# EyeControl.net
KiCad netlist of a schematic drawn in EAGLE
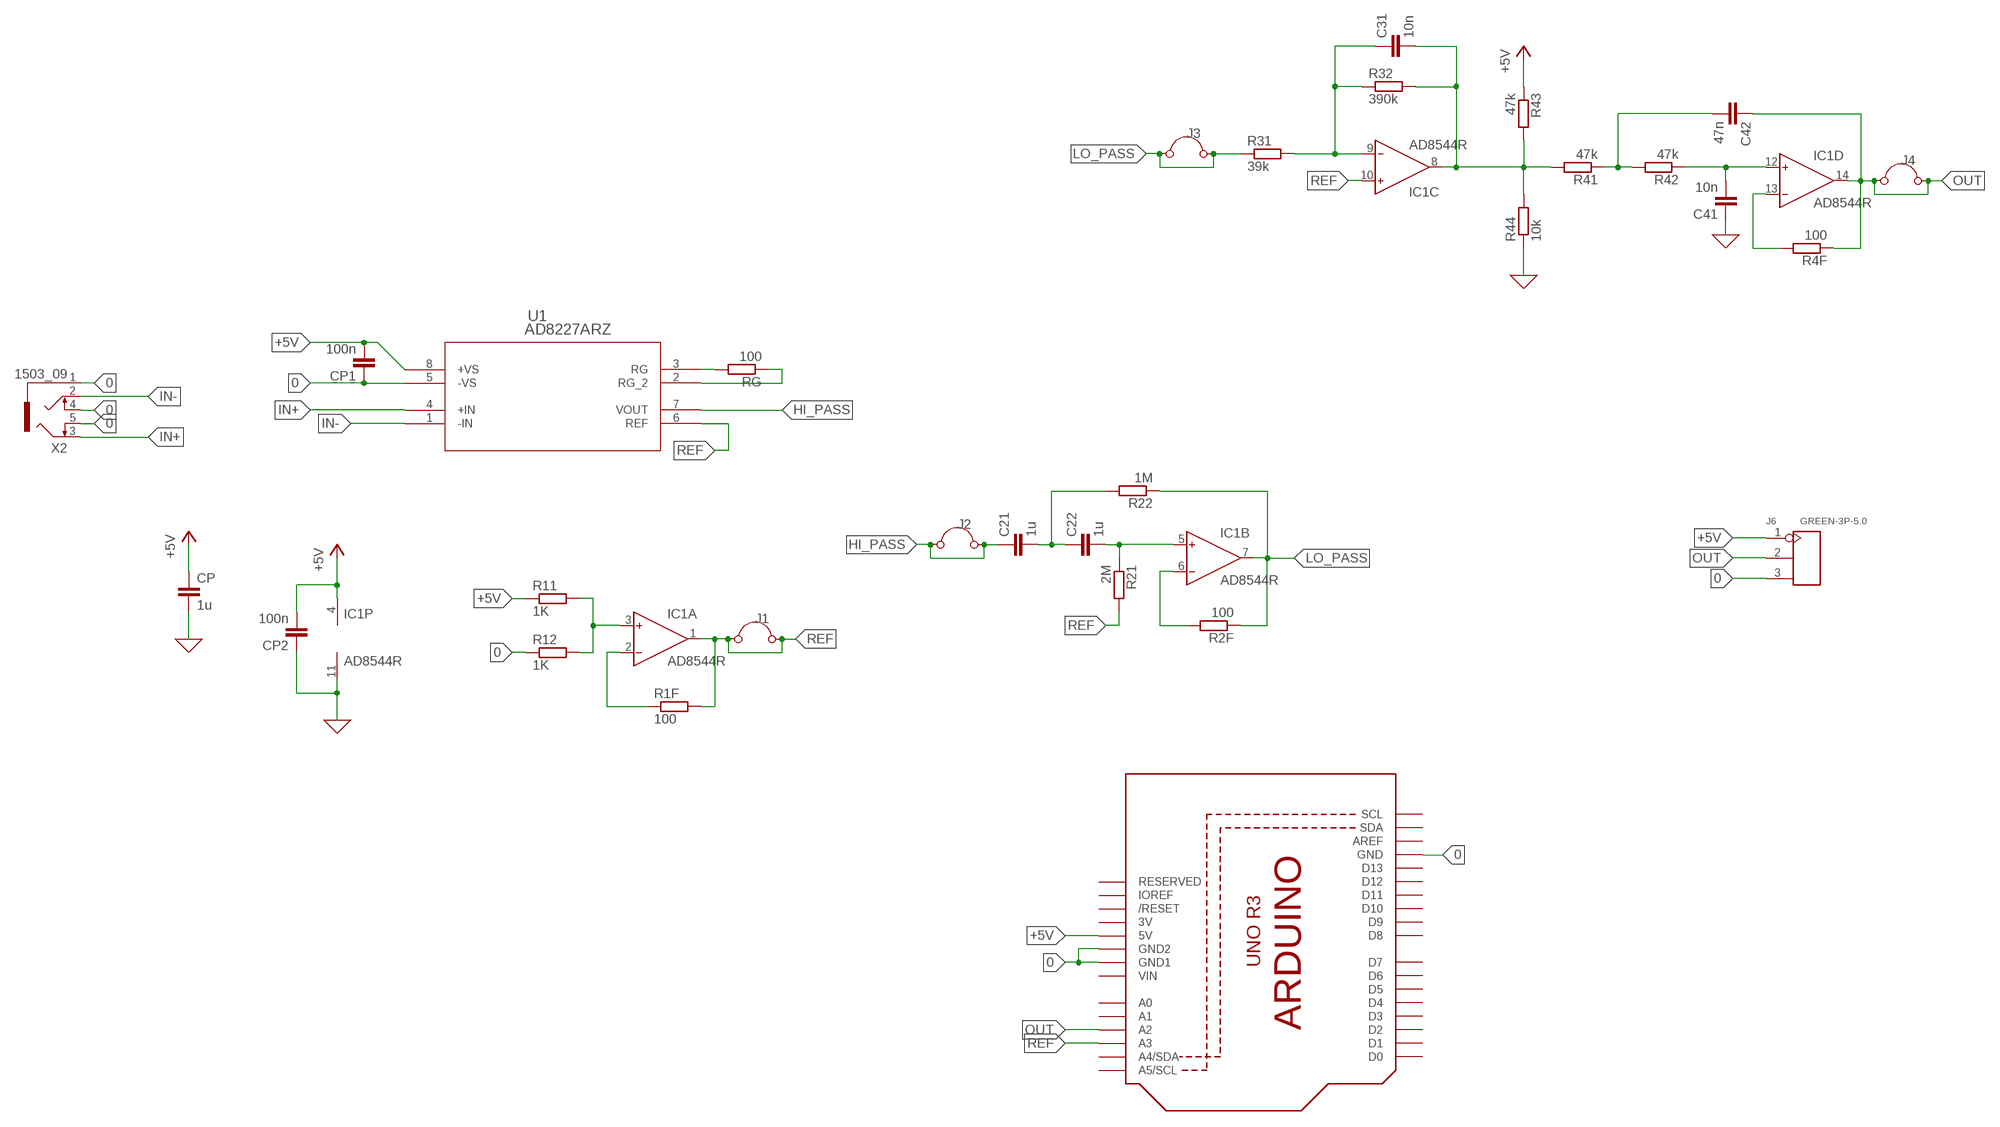
[diagram p0: schematic, sheet 1]

(export (version "E")
  (design (tool "Eeschema 10.0.6"))
  (components
    (comp (ref "C21")
      (value "1u")
      (footprint "eagle-import:C0805")
      (libsource (lib "eagle-import") (part "C"))
    )
    (comp (ref "C22")
      (value "1u")
      (footprint "eagle-import:C0805")
      (libsource (lib "eagle-import") (part "C"))
    )
    (comp (ref "C31")
      (value "10n")
      (footprint "eagle-import:C0805")
      (libsource (lib "eagle-import") (part "C"))
    )
    (comp (ref "C41")
      (value "10n")
      (footprint "eagle-import:C0805")
      (libsource (lib "eagle-import") (part "C"))
    )
    (comp (ref "C42")
      (value "47n")
      (footprint "eagle-import:C0805")
      (libsource (lib "eagle-import") (part "C"))
    )
    (comp (ref "CP")
      (value "1u")
      (footprint "eagle-import:C0805")
      (libsource (lib "eagle-import") (part "C"))
    )
    (comp (ref "CP1")
      (value "100n")
      (footprint "eagle-import:C0805")
      (libsource (lib "eagle-import") (part "C"))
    )
    (comp (ref "CP2")
      (value "100n")
      (footprint "eagle-import:C0805")
      (libsource (lib "eagle-import") (part "C"))
    )
    (comp (ref "IC1")
      (value "AD8544R")
      (footprint "eagle-import:SO14")
      (fields (field (name "MPN") "AD8544ARZ"))
      (libsource (lib "eagle-import") (part "AD8544R"))
    )
    (comp (ref "J1")
      (value "JUMPER")
      (footprint "eagle-import:05")
      (libsource (lib "eagle-import") (part "JUMPER"))
    )
    (comp (ref "J2")
      (value "JUMPER")
      (footprint "eagle-import:05")
      (libsource (lib "eagle-import") (part "JUMPER"))
    )
    (comp (ref "J3")
      (value "JUMPER")
      (footprint "eagle-import:05")
      (libsource (lib "eagle-import") (part "JUMPER"))
    )
    (comp (ref "J4")
      (value "JUMPER")
      (footprint "eagle-import:05")
      (libsource (lib "eagle-import") (part "JUMPER"))
    )
    (comp (ref "J6")
      (value "GREEN-3P-5.0")
      (footprint "eagle-import:H3-5.0-15.5X8.0MM")
      (libsource (lib "eagle-import") (part "SCREW-TERMINAL-GREEN(3P-5.0)"))
    )
    (comp (ref "R1F")
      (value "100")
      (footprint "eagle-import:R1206")
      (libsource (lib "eagle-import") (part "RR1206"))
    )
    (comp (ref "R2F")
      (value "100")
      (footprint "eagle-import:R1206")
      (libsource (lib "eagle-import") (part "RR1206"))
    )
    (comp (ref "R4F")
      (value "100")
      (footprint "eagle-import:R1206")
      (libsource (lib "eagle-import") (part "RR1206"))
    )
    (comp (ref "R11")
      (value "1K")
      (footprint "eagle-import:R1206")
      (libsource (lib "eagle-import") (part "RR1206"))
    )
    (comp (ref "R12")
      (value "1K")
      (footprint "eagle-import:R1206")
      (libsource (lib "eagle-import") (part "RR1206"))
    )
    (comp (ref "R21")
      (value "2M")
      (footprint "eagle-import:R1206")
      (libsource (lib "eagle-import") (part "RR1206"))
    )
    (comp (ref "R22")
      (value "1M")
      (footprint "eagle-import:R1206")
      (libsource (lib "eagle-import") (part "RR1206"))
    )
    (comp (ref "R31")
      (value "39k")
      (footprint "eagle-import:R1206")
      (libsource (lib "eagle-import") (part "RR1206"))
    )
    (comp (ref "R32")
      (value "390k")
      (footprint "eagle-import:R1206")
      (libsource (lib "eagle-import") (part "RR1206"))
    )
    (comp (ref "R41")
      (value "47k")
      (footprint "eagle-import:R1206")
      (libsource (lib "eagle-import") (part "RR1206"))
    )
    (comp (ref "R42")
      (value "47k")
      (footprint "eagle-import:R1206")
      (libsource (lib "eagle-import") (part "RR1206"))
    )
    (comp (ref "R43")
      (value "47k")
      (footprint "eagle-import:R1206")
      (libsource (lib "eagle-import") (part "RR1206"))
    )
    (comp (ref "R44")
      (value "10k")
      (footprint "eagle-import:R1206")
      (libsource (lib "eagle-import") (part "RR1206"))
    )
    (comp (ref "RG")
      (value "100")
      (footprint "eagle-import:R1206")
      (libsource (lib "eagle-import") (part "RR1206"))
    )
    (comp (ref "U$1")
      (value "ARDUINOR3-DIMENSION")
      (footprint "eagle-import:ARDUINOR3")
      (libsource (lib "eagle-import") (part "ARDUINOR3-DIMENSION"))
    )
    (comp (ref "U1")
      (value "AD8227ARZ")
      (footprint "eagle-import:R_8")
      (libsource (lib "eagle-import") (part "AD8227ARZ"))
    )
    (comp (ref "X2")
      (value "1503_09")
      (footprint "eagle-import:1503_09")
      (libsource (lib "eagle-import") (part "1503_09"))
    )
  )
  (nets
    (net (code "1") (name "+5V") (class "Default")
      (node (ref "CP") (pin "1") (pinfunction "1_1") (pintype "passive"))
      (node (ref "CP1") (pin "2") (pinfunction "2_2") (pintype "passive"))
      (node (ref "CP2") (pin "2") (pinfunction "2_2") (pintype "passive"))
      (node (ref "IC1") (pin "4") (pinfunction "V+_4") (pintype "power_in"))
      (node (ref "J6") (pin "1") (pinfunction "P$1_1") (pintype "bidirectional"))
      (node (ref "R11") (pin "1") (pinfunction "1_1") (pintype "passive"))
      (node (ref "R43") (pin "1") (pinfunction "1_1") (pintype "passive"))
      (node (ref "U$1") (pin "5V") (pinfunction "5V_5V") (pintype "power_in"))
      (node (ref "U1") (pin "8") (pinfunction "+VS_8") (pintype "power_in"))
    )
    (net (code "2") (name "/3V") (class "Default")
      (node (ref "U$1") (pin "3V") (pinfunction "3V_3V") (pintype "power_in"))
    )
    (net (code "3") (name "/VIN") (class "Default")
      (node (ref "U$1") (pin "VIN") (pinfunction "VIN_VIN") (pintype "power_in"))
    )
    (net (code "4") (name "0") (class "Default")
      (node (ref "C41") (pin "1") (pinfunction "1_1") (pintype "passive"))
      (node (ref "CP") (pin "2") (pinfunction "2_2") (pintype "passive"))
      (node (ref "CP1") (pin "1") (pinfunction "1_1") (pintype "passive"))
      (node (ref "CP2") (pin "1") (pinfunction "1_1") (pintype "passive"))
      (node (ref "IC1") (pin "11") (pinfunction "V-_11") (pintype "power_in"))
      (node (ref "J6") (pin "3") (pinfunction "P$3_3") (pintype "bidirectional"))
      (node (ref "R12") (pin "1") (pinfunction "1_1") (pintype "passive"))
      (node (ref "R44") (pin "1") (pinfunction "1_1") (pintype "passive"))
      (node (ref "U$1") (pin "GND") (pinfunction "GND_GND") (pintype "power_in"))
      (node (ref "U$1") (pin "GND1") (pinfunction "GND1_GND1") (pintype "power_in"))
      (node (ref "U$1") (pin "GND2") (pinfunction "GND2_GND2") (pintype "power_in"))
      (node (ref "U1") (pin "5") (pinfunction "-VS_5") (pintype "power_in"))
      (node (ref "X2") (pin "1") (pinfunction "1_1") (pintype "passive"))
      (node (ref "X2") (pin "4") (pinfunction "4_4") (pintype "passive"))
      (node (ref "X2") (pin "5") (pinfunction "5_5") (pintype "passive"))
    )
    (net (code "5") (name "HI_PASS") (class "Default")
      (node (ref "C21") (pin "1") (pinfunction "1_1") (pintype "passive"))
      (node (ref "J2") (pin "1") (pinfunction "+_1") (pintype "passive"))
      (node (ref "J2") (pin "2") (pinfunction "-_2") (pintype "passive"))
      (node (ref "U1") (pin "7") (pinfunction "VOUT_7") (pintype "output"))
    )
    (net (code "6") (name "IN+") (class "Default")
      (node (ref "U1") (pin "4") (pinfunction "+IN_4") (pintype "input"))
      (node (ref "X2") (pin "3") (pinfunction "3_3") (pintype "passive"))
    )
    (net (code "7") (name "IN-") (class "Default")
      (node (ref "U1") (pin "1") (pinfunction "-IN_1") (pintype "input"))
      (node (ref "X2") (pin "2") (pinfunction "2_2") (pintype "passive"))
    )
    (net (code "8") (name "LO_PASS") (class "Default")
      (node (ref "IC1") (pin "7") (pinfunction "OUT_7") (pintype "output"))
      (node (ref "J3") (pin "1") (pinfunction "+_1") (pintype "passive"))
      (node (ref "J3") (pin "2") (pinfunction "-_2") (pintype "passive"))
      (node (ref "R22") (pin "1") (pinfunction "1_1") (pintype "passive"))
      (node (ref "R2F") (pin "1") (pinfunction "1_1") (pintype "passive"))
      (node (ref "R31") (pin "1") (pinfunction "1_1") (pintype "passive"))
    )
    (net (code "9") (name "Net-(C21-Pad2)") (class "Default")
      (node (ref "C21") (pin "2") (pinfunction "2_2") (pintype "passive"))
      (node (ref "C22") (pin "1") (pinfunction "1_1") (pintype "passive"))
      (node (ref "R22") (pin "2") (pinfunction "2_2") (pintype "passive"))
    )
    (net (code "10") (name "Net-(C42-Pad2)") (class "Default")
      (node (ref "C42") (pin "2") (pinfunction "2_2") (pintype "passive"))
      (node (ref "R41") (pin "1") (pinfunction "1_1") (pintype "passive"))
      (node (ref "R42") (pin "2") (pinfunction "2_2") (pintype "passive"))
    )
    (net (code "11") (name "Net-(IC1A-IN+)") (class "Default")
      (node (ref "IC1") (pin "3") (pinfunction "IN+_3") (pintype "input"))
      (node (ref "R11") (pin "2") (pinfunction "2_2") (pintype "passive"))
      (node (ref "R12") (pin "2") (pinfunction "2_2") (pintype "passive"))
    )
    (net (code "12") (name "Net-(IC1A-IN-)") (class "Default")
      (node (ref "IC1") (pin "2") (pinfunction "IN-_2") (pintype "input"))
      (node (ref "R1F") (pin "1") (pinfunction "1_1") (pintype "passive"))
    )
    (net (code "13") (name "Net-(IC1B-IN+)") (class "Default")
      (node (ref "C22") (pin "2") (pinfunction "2_2") (pintype "passive"))
      (node (ref "IC1") (pin "5") (pinfunction "IN+_5") (pintype "input"))
      (node (ref "R21") (pin "1") (pinfunction "1_1") (pintype "passive"))
    )
    (net (code "14") (name "Net-(IC1B-IN-)") (class "Default")
      (node (ref "IC1") (pin "6") (pinfunction "IN-_6") (pintype "input"))
      (node (ref "R2F") (pin "2") (pinfunction "2_2") (pintype "passive"))
    )
    (net (code "15") (name "Net-(IC1C-IN-)") (class "Default")
      (node (ref "C31") (pin "1") (pinfunction "1_1") (pintype "passive"))
      (node (ref "IC1") (pin "9") (pinfunction "IN-_9") (pintype "input"))
      (node (ref "R31") (pin "2") (pinfunction "2_2") (pintype "passive"))
      (node (ref "R32") (pin "1") (pinfunction "1_1") (pintype "passive"))
    )
    (net (code "16") (name "Net-(IC1C-OUT)") (class "Default")
      (node (ref "C31") (pin "2") (pinfunction "2_2") (pintype "passive"))
      (node (ref "IC1") (pin "8") (pinfunction "OUT_8") (pintype "output"))
      (node (ref "R32") (pin "2") (pinfunction "2_2") (pintype "passive"))
      (node (ref "R41") (pin "2") (pinfunction "2_2") (pintype "passive"))
      (node (ref "R43") (pin "2") (pinfunction "2_2") (pintype "passive"))
      (node (ref "R44") (pin "2") (pinfunction "2_2") (pintype "passive"))
    )
    (net (code "17") (name "Net-(IC1D-IN+)") (class "Default")
      (node (ref "C41") (pin "2") (pinfunction "2_2") (pintype "passive"))
      (node (ref "IC1") (pin "12") (pinfunction "IN+_12") (pintype "input"))
      (node (ref "R42") (pin "1") (pinfunction "1_1") (pintype "passive"))
    )
    (net (code "18") (name "Net-(IC1D-IN-)") (class "Default")
      (node (ref "IC1") (pin "13") (pinfunction "IN-_13") (pintype "input"))
      (node (ref "R4F") (pin "2") (pinfunction "2_2") (pintype "passive"))
    )
    (net (code "19") (name "Net-(U1-RG)") (class "Default")
      (node (ref "RG") (pin "2") (pinfunction "2_2") (pintype "passive"))
      (node (ref "U1") (pin "3") (pinfunction "RG_3") (pintype "passive"))
    )
    (net (code "20") (name "Net-(U1-RG_2)") (class "Default")
      (node (ref "RG") (pin "1") (pinfunction "1_1") (pintype "passive"))
      (node (ref "U1") (pin "2") (pinfunction "RG_2_2") (pintype "passive"))
    )
    (net (code "21") (name "OUT") (class "Default")
      (node (ref "C42") (pin "1") (pinfunction "1_1") (pintype "passive"))
      (node (ref "IC1") (pin "14") (pinfunction "OUT_14") (pintype "output"))
      (node (ref "J4") (pin "1") (pinfunction "+_1") (pintype "passive"))
      (node (ref "J4") (pin "2") (pinfunction "-_2") (pintype "passive"))
      (node (ref "J6") (pin "2") (pinfunction "P$2_2") (pintype "bidirectional"))
      (node (ref "R4F") (pin "1") (pinfunction "1_1") (pintype "passive"))
      (node (ref "U$1") (pin "A2") (pinfunction "A2_A2") (pintype "bidirectional"))
    )
    (net (code "22") (name "REF") (class "Default")
      (node (ref "IC1") (pin "1") (pinfunction "OUT_1") (pintype "output"))
      (node (ref "IC1") (pin "10") (pinfunction "IN+_10") (pintype "input"))
      (node (ref "J1") (pin "1") (pinfunction "+_1") (pintype "passive"))
      (node (ref "J1") (pin "2") (pinfunction "-_2") (pintype "passive"))
      (node (ref "R1F") (pin "2") (pinfunction "2_2") (pintype "passive"))
      (node (ref "R21") (pin "2") (pinfunction "2_2") (pintype "passive"))
      (node (ref "U$1") (pin "A3") (pinfunction "A3_A3") (pintype "bidirectional"))
      (node (ref "U1") (pin "6") (pinfunction "REF_6") (pintype "output"))
    )
    (net (code "23") (name "unconnected-(U$1-A4{slash}SDA-PadA4)") (class "Default")
      (node (ref "U$1") (pin "A4") (pinfunction "A4/SDA_A4") (pintype "bidirectional"))
    )
    (net (code "24") (name "unconnected-(U$1-A5{slash}SCL-PadA5)") (class "Default")
      (node (ref "U$1") (pin "A5") (pinfunction "A5/SCL_A5") (pintype "bidirectional"))
    )
    (net (code "25") (name "unconnected-(U$1-PadA0)") (class "Default")
      (node (ref "U$1") (pin "A0") (pinfunction "A0_A0") (pintype "bidirectional"))
    )
    (net (code "26") (name "unconnected-(U$1-PadA1)") (class "Default")
      (node (ref "U$1") (pin "A1") (pinfunction "A1_A1") (pintype "bidirectional"))
    )
    (net (code "27") (name "unconnected-(U$1-PadAREF)") (class "Default")
      (node (ref "U$1") (pin "AREF") (pinfunction "AREF_AREF") (pintype "bidirectional"))
    )
    (net (code "28") (name "unconnected-(U$1-PadD0)") (class "Default")
      (node (ref "U$1") (pin "D0") (pinfunction "D0_D0") (pintype "bidirectional"))
    )
    (net (code "29") (name "unconnected-(U$1-PadD1)") (class "Default")
      (node (ref "U$1") (pin "D1") (pinfunction "D1_D1") (pintype "bidirectional"))
    )
    (net (code "30") (name "unconnected-(U$1-PadD2)") (class "Default")
      (node (ref "U$1") (pin "D2") (pinfunction "D2_D2") (pintype "bidirectional"))
    )
    (net (code "31") (name "unconnected-(U$1-PadD3)") (class "Default")
      (node (ref "U$1") (pin "D3") (pinfunction "D3_D3") (pintype "bidirectional"))
    )
    (net (code "32") (name "unconnected-(U$1-PadD4)") (class "Default")
      (node (ref "U$1") (pin "D4") (pinfunction "D4_D4") (pintype "bidirectional"))
    )
    (net (code "33") (name "unconnected-(U$1-PadD5)") (class "Default")
      (node (ref "U$1") (pin "D5") (pinfunction "D5_D5") (pintype "bidirectional"))
    )
    (net (code "34") (name "unconnected-(U$1-PadD6)") (class "Default")
      (node (ref "U$1") (pin "D6") (pinfunction "D6_D6") (pintype "bidirectional"))
    )
    (net (code "35") (name "unconnected-(U$1-PadD7)") (class "Default")
      (node (ref "U$1") (pin "D7") (pinfunction "D7_D7") (pintype "bidirectional"))
    )
    (net (code "36") (name "unconnected-(U$1-PadD8)") (class "Default")
      (node (ref "U$1") (pin "D8") (pinfunction "D8_D8") (pintype "bidirectional"))
    )
    (net (code "37") (name "unconnected-(U$1-PadD9)") (class "Default")
      (node (ref "U$1") (pin "D9") (pinfunction "D9_D9") (pintype "bidirectional"))
    )
    (net (code "38") (name "unconnected-(U$1-PadD10)") (class "Default")
      (node (ref "U$1") (pin "D10") (pinfunction "D10_D10") (pintype "bidirectional"))
    )
    (net (code "39") (name "unconnected-(U$1-PadD11)") (class "Default")
      (node (ref "U$1") (pin "D11") (pinfunction "D11_D11") (pintype "bidirectional"))
    )
    (net (code "40") (name "unconnected-(U$1-PadD12)") (class "Default")
      (node (ref "U$1") (pin "D12") (pinfunction "D12_D12") (pintype "bidirectional"))
    )
    (net (code "41") (name "unconnected-(U$1-PadD13)") (class "Default")
      (node (ref "U$1") (pin "D13") (pinfunction "D13_D13") (pintype "bidirectional"))
    )
    (net (code "42") (name "unconnected-(U$1-PadIOREF)") (class "Default")
      (node (ref "U$1") (pin "IOREF") (pinfunction "IOREF_IOREF") (pintype "output"))
    )
    (net (code "43") (name "unconnected-(U$1-PadRESERVED)") (class "Default")
      (node (ref "U$1") (pin "RESERVED") (pinfunction "RESERVED_RESERVED") (pintype "no_connect"))
    )
    (net (code "44") (name "unconnected-(U$1-PadSCL)") (class "Default")
      (node (ref "U$1") (pin "SCL") (pinfunction "SCL_SCL") (pintype "bidirectional"))
    )
    (net (code "45") (name "unconnected-(U$1-PadSDA)") (class "Default")
      (node (ref "U$1") (pin "SDA") (pinfunction "SDA_SDA") (pintype "bidirectional"))
    )
    (net (code "46") (name "unconnected-(U$1-{slash}RESET-PadRESET)") (class "Default")
      (node (ref "U$1") (pin "RESET") (pinfunction "/RESET_RESET") (pintype "bidirectional"))
    )
  )
)
